# NTC_Thermistor_10K_VDiv_wBuffer.net
KiCad netlist of a schematic drawn in Altium Designer
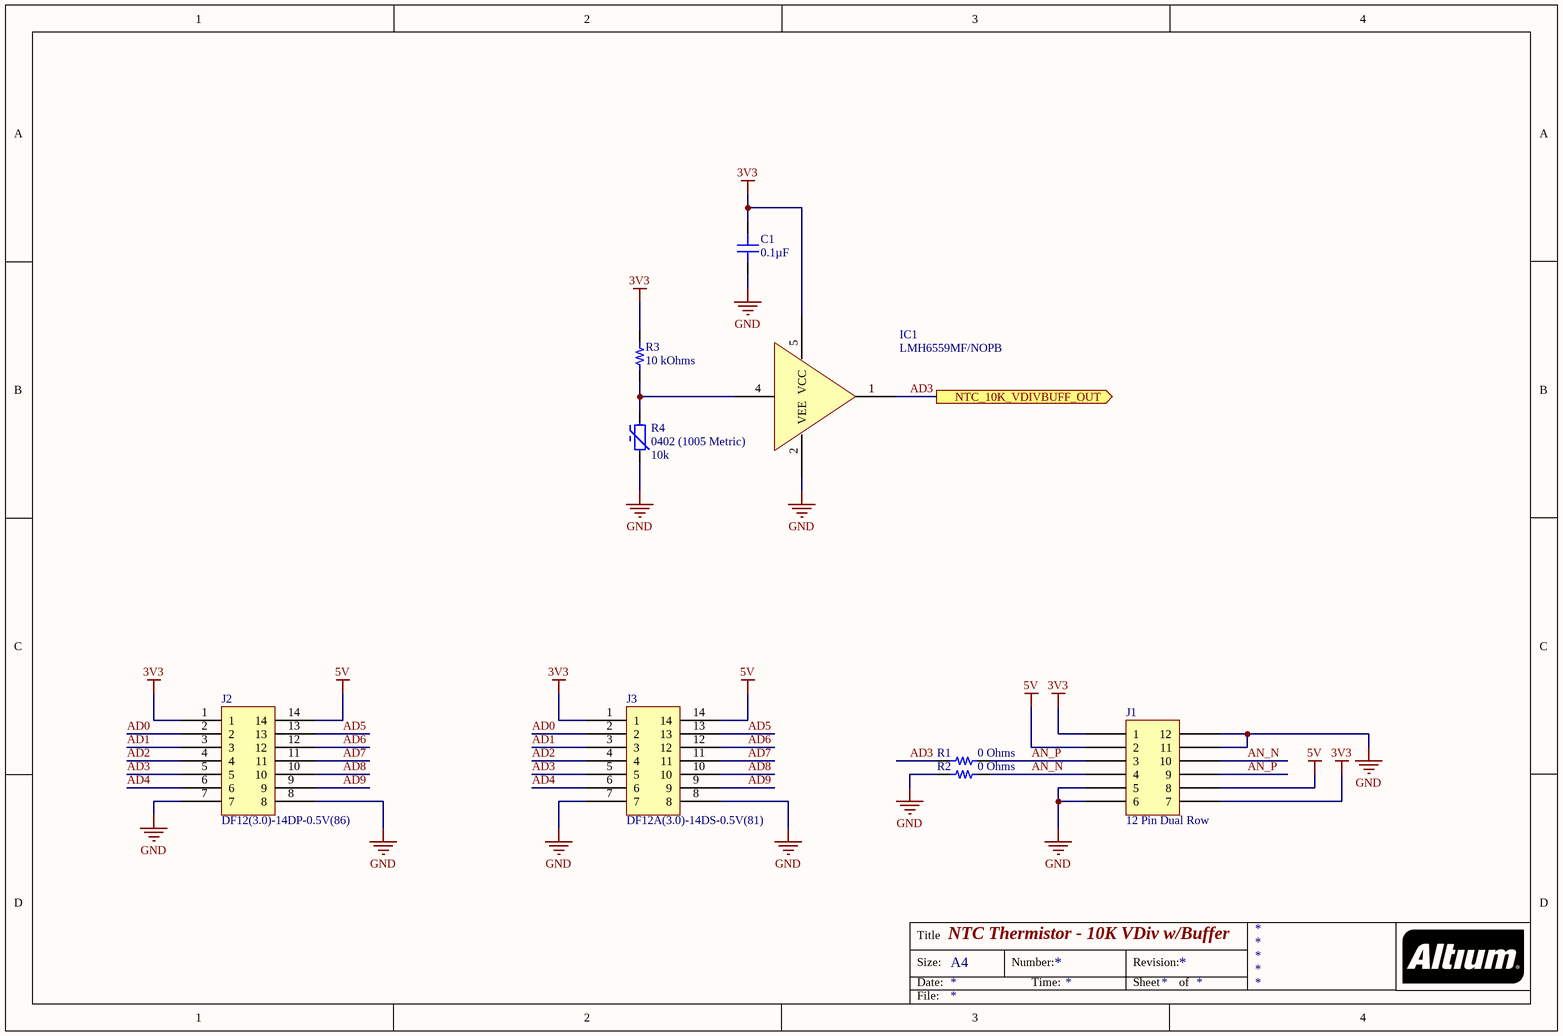
[diagram p0: NTC Thermistor 10K VDiv wBuffer.SchDoc]

(export (version "E")
  (design (tool "Eeschema 10.0.6"))
  (components
    (comp (ref "C1")
      (value "0.1µF")
      (footprint "CAP 0603_1608")
      (description "CAP CER 0.1UF 16V Y5V 0603")
      (fields (field (name "PART NUMBER") "CC0603ZRY5V7BB104") (field (name "MANUFACTURER") "Yageo"))
      (libsource (lib "altiumlibrary.com") (part "Capacitor"))
    )
    (comp (ref "IC1")
      (value "LMH6559MF/NOPB")
      (footprint "TI SOT-23-5 DBV")
      (description "IC BUFFER 1 CIRCUIT SOT23-5")
      (fields (field (name "MANUFACTURER") "Texas Instruments"))
      (libsource (lib "altiumlibrary.com") (part "TI LMH6559"))
    )
    (comp (ref "J1")
      (value "12 Pin Dual Row")
      (footprint "TE 5650118-3 Card Edge")
      (libsource (lib "CelestialUseful") (part "12 Pin Dual Row"))
    )
    (comp (ref "J2")
      (value "DF12(3.0)-14DP-0.5V(86)")
      (footprint "HIROSE DF12 3.0-14DP-0.5V 86")
      (description "CONN HDR 14POS SMD GOLD")
      (fields (field (name "MANUFACTURER") "Hirose Electric Co Ltd"))
      (libsource (lib "altiumlibrary.com") (part "14 Pin Dual Row"))
    )
    (comp (ref "J3")
      (value "DF12A(3.0)-14DS-0.5V(81)")
      (footprint "HIROSE DF12A 3.0-14DS-0.5V 81")
      (description "CONN RCPT 14POS SMD GOLD")
      (fields (field (name "MANUFACTURER") "Hirose Electric Co Ltd"))
      (libsource (lib "altiumlibrary.com") (part "14 Pin Dual Row"))
    )
    (comp (ref "R1")
      (value "0 Ohms")
      (footprint "RES 0603_1608")
      (description "RES SMD 0 OHM JUMPER 1/10W 0603")
      (fields
        (field (name "PART NUMBER") "ERJ-3GEY0R00V")
        (field (name "MANUFACTURER") "Panasonic Electronic Components")
      )
      (libsource (lib "altiumlibrary.com") (part "Resistor"))
    )
    (comp (ref "R2")
      (value "0 Ohms")
      (footprint "RES 0603_1608")
      (description "RES SMD 0 OHM JUMPER 1/10W 0603")
      (fields
        (field (name "PART NUMBER") "ERJ-3GEY0R00V")
        (field (name "MANUFACTURER") "Panasonic Electronic Components")
      )
      (libsource (lib "altiumlibrary.com") (part "Resistor"))
    )
    (comp (ref "R3")
      (value "10 kOhms")
      (footprint "RES 0603_1608")
      (description "RES SMD 10K OHM 1% 1/10W 0603")
      (fields
        (field (name "PART NUMBER") "ERJ-3EKF1002V")
        (field (name "MANUFACTURER") "Panasonic Electronic Components")
      )
      (libsource (lib "altiumlibrary.com") (part "Resistor"))
    )
    (comp (ref "R4")
      (value "NCP15XH103F03RC")
      (footprint "NTC 0402_1005")
      (description "THERMISTOR NTC 10KOHM 3380K 0402")
      (fields
        (field (name "MANUFACTURER") "Murata Electronics")
        (field (name "PACKAGE / CASE") "0402 (1005 Metric)")
        (field (name "RESISTANCE IN OHMS @ 25°C") "10k")
      )
      (libsource (lib "altiumlibrary.com") (part "Thermistor"))
    )
  )
  (nets
    (net (code "1") (name "/AD0") (class "Default")
      (node (ref "J2") (pin "2") (pinfunction "2_2") (pintype "passive"))
      (node (ref "J3") (pin "2") (pinfunction "2_2") (pintype "passive"))
    )
    (net (code "2") (name "/AD1") (class "Default")
      (node (ref "J2") (pin "3") (pinfunction "3_3") (pintype "passive"))
      (node (ref "J3") (pin "3") (pinfunction "3_3") (pintype "passive"))
    )
    (net (code "3") (name "/AD2") (class "Default")
      (node (ref "J2") (pin "4") (pinfunction "4_4") (pintype "passive"))
      (node (ref "J3") (pin "4") (pinfunction "4_4") (pintype "passive"))
    )
    (net (code "4") (name "/AD3") (class "Default")
      (node (ref "IC1") (pin "1") (pinfunction "OUT_1") (pintype "passive"))
      (node (ref "J2") (pin "5") (pinfunction "5_5") (pintype "passive"))
      (node (ref "J3") (pin "5") (pinfunction "5_5") (pintype "passive"))
      (node (ref "R1") (pin "1") (pinfunction "1_1") (pintype "passive"))
    )
    (net (code "5") (name "/AD4") (class "Default")
      (node (ref "J2") (pin "6") (pinfunction "6_6") (pintype "passive"))
      (node (ref "J3") (pin "6") (pinfunction "6_6") (pintype "passive"))
    )
    (net (code "6") (name "/AD5") (class "Default")
      (node (ref "J2") (pin "13") (pinfunction "13_13") (pintype "passive"))
      (node (ref "J3") (pin "13") (pinfunction "13_13") (pintype "passive"))
    )
    (net (code "7") (name "/AD6") (class "Default")
      (node (ref "J2") (pin "12") (pinfunction "12_12") (pintype "passive"))
      (node (ref "J3") (pin "12") (pinfunction "12_12") (pintype "passive"))
    )
    (net (code "8") (name "/AD7") (class "Default")
      (node (ref "J2") (pin "11") (pinfunction "11_11") (pintype "passive"))
      (node (ref "J3") (pin "11") (pinfunction "11_11") (pintype "passive"))
    )
    (net (code "9") (name "/AD8") (class "Default")
      (node (ref "J2") (pin "10") (pinfunction "10_10") (pintype "passive"))
      (node (ref "J3") (pin "10") (pinfunction "10_10") (pintype "passive"))
    )
    (net (code "10") (name "/AD9") (class "Default")
      (node (ref "J2") (pin "9") (pinfunction "9_9") (pintype "passive"))
      (node (ref "J3") (pin "9") (pinfunction "9_9") (pintype "passive"))
    )
    (net (code "11") (name "/AN_N") (class "Default")
      (node (ref "J1") (pin "10") (pinfunction "10_10") (pintype "passive"))
      (node (ref "J1") (pin "4") (pinfunction "4_4") (pintype "passive"))
      (node (ref "R2") (pin "2") (pinfunction "2_2") (pintype "passive"))
    )
    (net (code "12") (name "/AN_P") (class "Default")
      (node (ref "J1") (pin "3") (pinfunction "3_3") (pintype "passive"))
      (node (ref "J1") (pin "9") (pinfunction "9_9") (pintype "passive"))
      (node (ref "R1") (pin "2") (pinfunction "2_2") (pintype "passive"))
    )
    (net (code "13") (name "3V3") (class "Default")
      (node (ref "C1") (pin "2") (pinfunction "2_2") (pintype "passive"))
      (node (ref "IC1") (pin "5") (pinfunction "VCC_5") (pintype "power_in"))
      (node (ref "J1") (pin "1") (pinfunction "1_1") (pintype "passive"))
      (node (ref "J1") (pin "7") (pinfunction "7_7") (pintype "passive"))
      (node (ref "J2") (pin "1") (pinfunction "1_1") (pintype "passive"))
      (node (ref "J3") (pin "1") (pinfunction "1_1") (pintype "passive"))
      (node (ref "R3") (pin "2") (pinfunction "2_2") (pintype "passive"))
    )
    (net (code "14") (name "5V") (class "Default")
      (node (ref "J1") (pin "2") (pinfunction "2_2") (pintype "passive"))
      (node (ref "J1") (pin "8") (pinfunction "8_8") (pintype "passive"))
      (node (ref "J2") (pin "14") (pinfunction "14_14") (pintype "passive"))
      (node (ref "J3") (pin "14") (pinfunction "14_14") (pintype "passive"))
    )
    (net (code "15") (name "GND") (class "Default")
      (node (ref "C1") (pin "1") (pinfunction "1_1") (pintype "passive"))
      (node (ref "IC1") (pin "2") (pinfunction "VEE_2") (pintype "power_in"))
      (node (ref "J1") (pin "11") (pinfunction "11_11") (pintype "passive"))
      (node (ref "J1") (pin "12") (pinfunction "12_12") (pintype "passive"))
      (node (ref "J1") (pin "5") (pinfunction "5_5") (pintype "passive"))
      (node (ref "J1") (pin "6") (pinfunction "6_6") (pintype "passive"))
      (node (ref "J2") (pin "7") (pinfunction "7_7") (pintype "passive"))
      (node (ref "J2") (pin "8") (pinfunction "8_8") (pintype "passive"))
      (node (ref "J3") (pin "7") (pinfunction "7_7") (pintype "passive"))
      (node (ref "J3") (pin "8") (pinfunction "8_8") (pintype "passive"))
      (node (ref "R2") (pin "1") (pinfunction "1_1") (pintype "passive"))
      (node (ref "R4") (pin "2") (pinfunction "2_2") (pintype "passive"))
    )
    (net (code "16") (name "Net-(IC1-IN)") (class "Default")
      (node (ref "IC1") (pin "4") (pinfunction "IN_4") (pintype "passive"))
      (node (ref "R3") (pin "1") (pinfunction "1_1") (pintype "passive"))
      (node (ref "R4") (pin "1") (pinfunction "1_1") (pintype "passive"))
    )
  )
)
